# WZ8048C050-V1_1-20230407.net
KiCad netlist of a schematic drawn in EAGLE
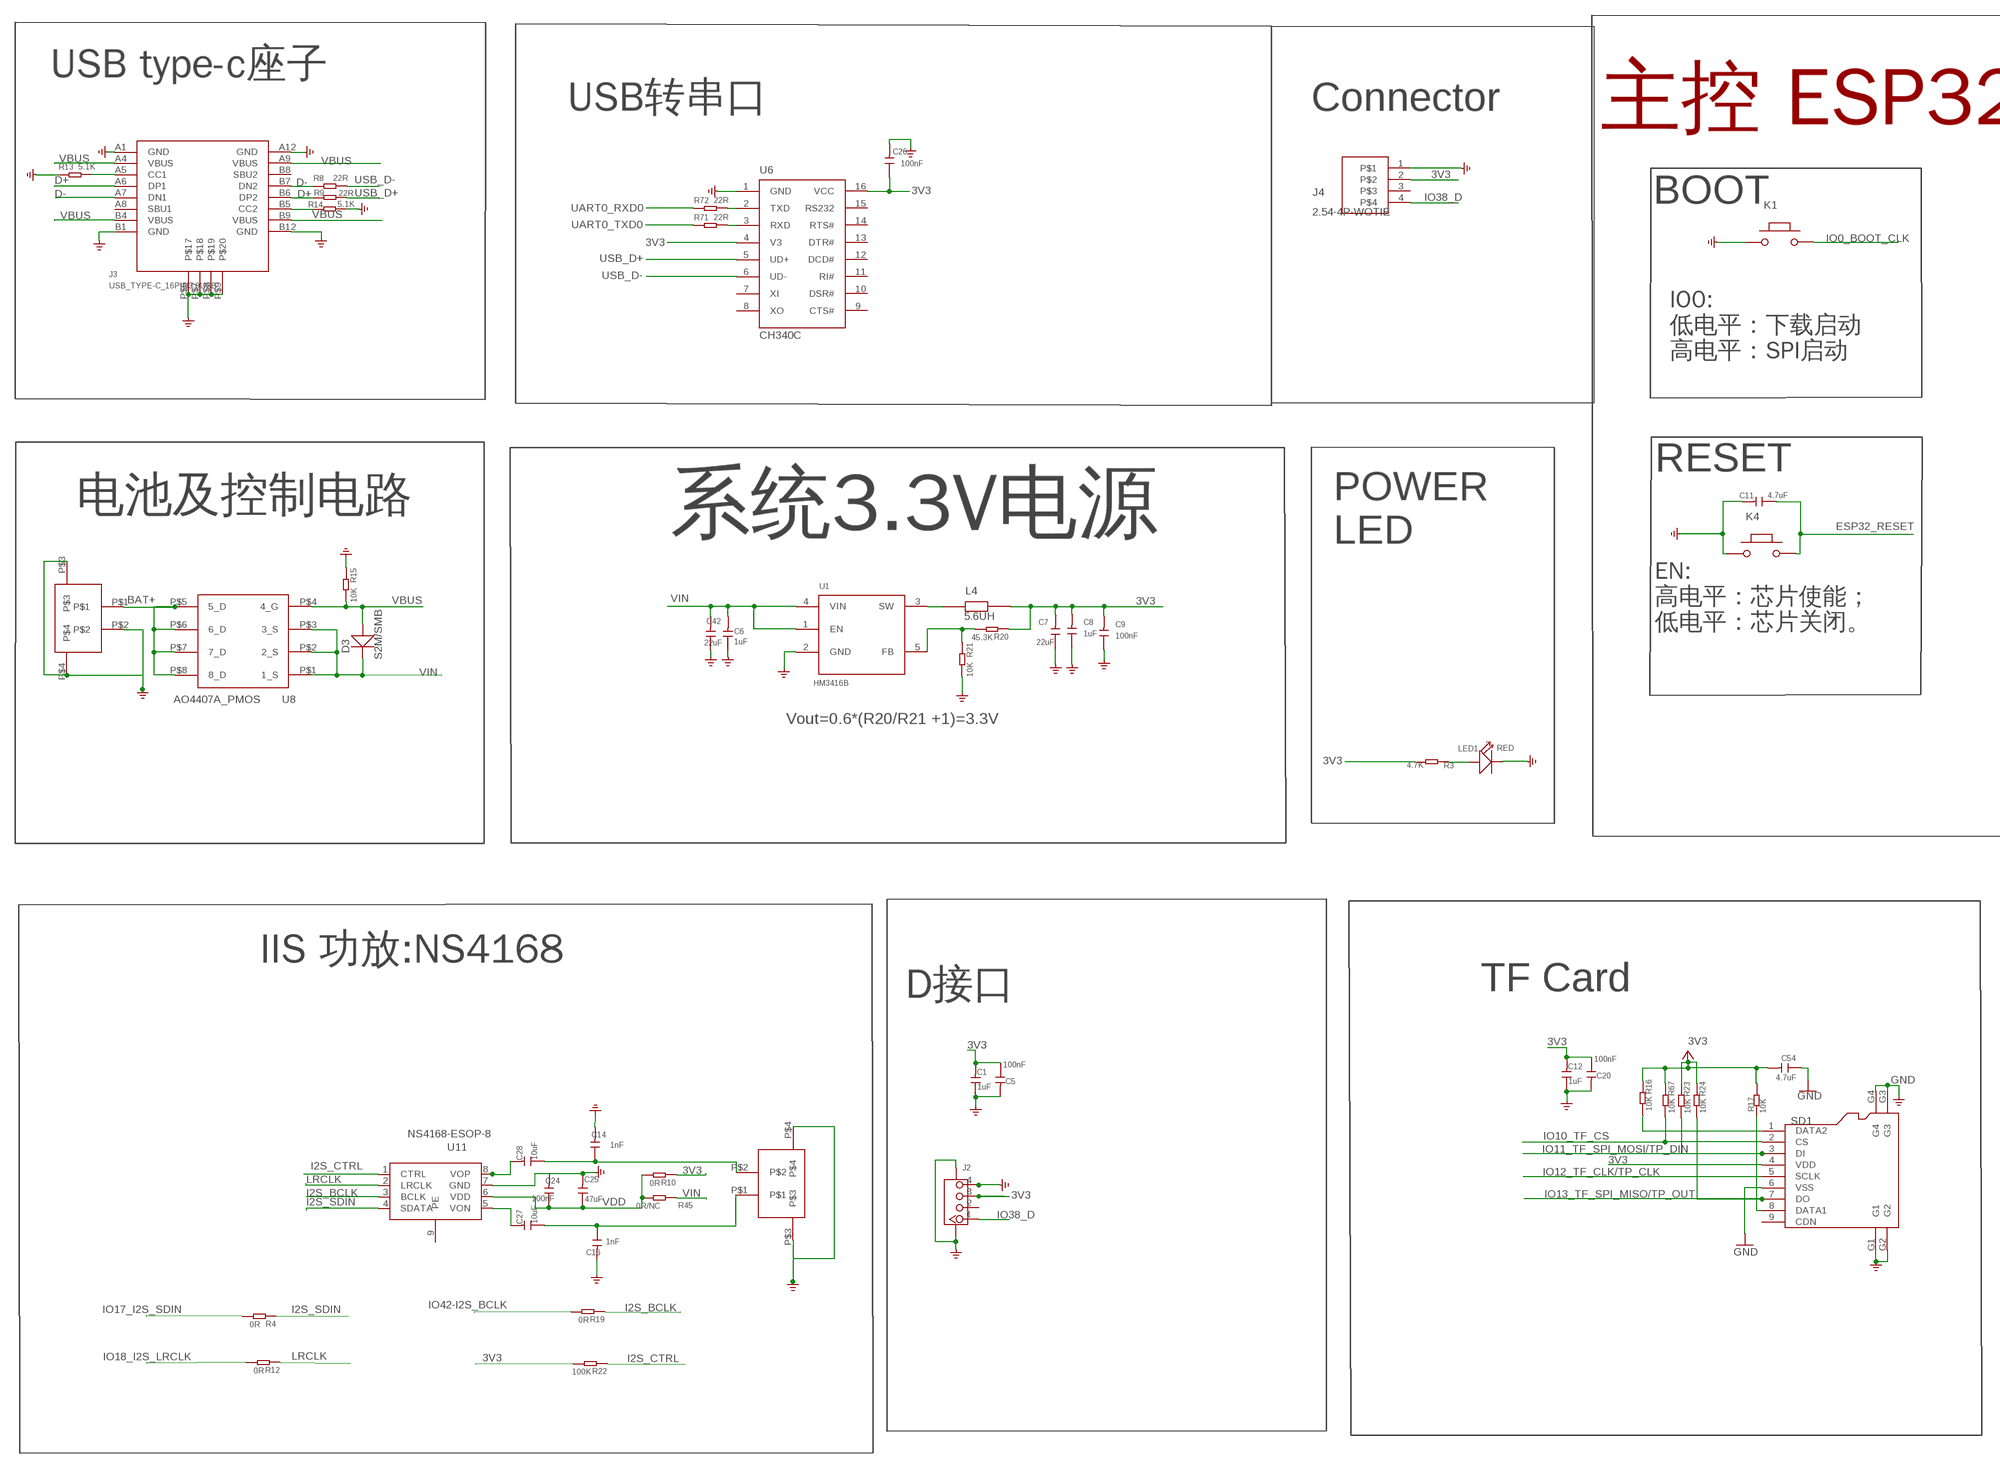
[diagram p0: schematic, sheet 1, part 1 of 2]
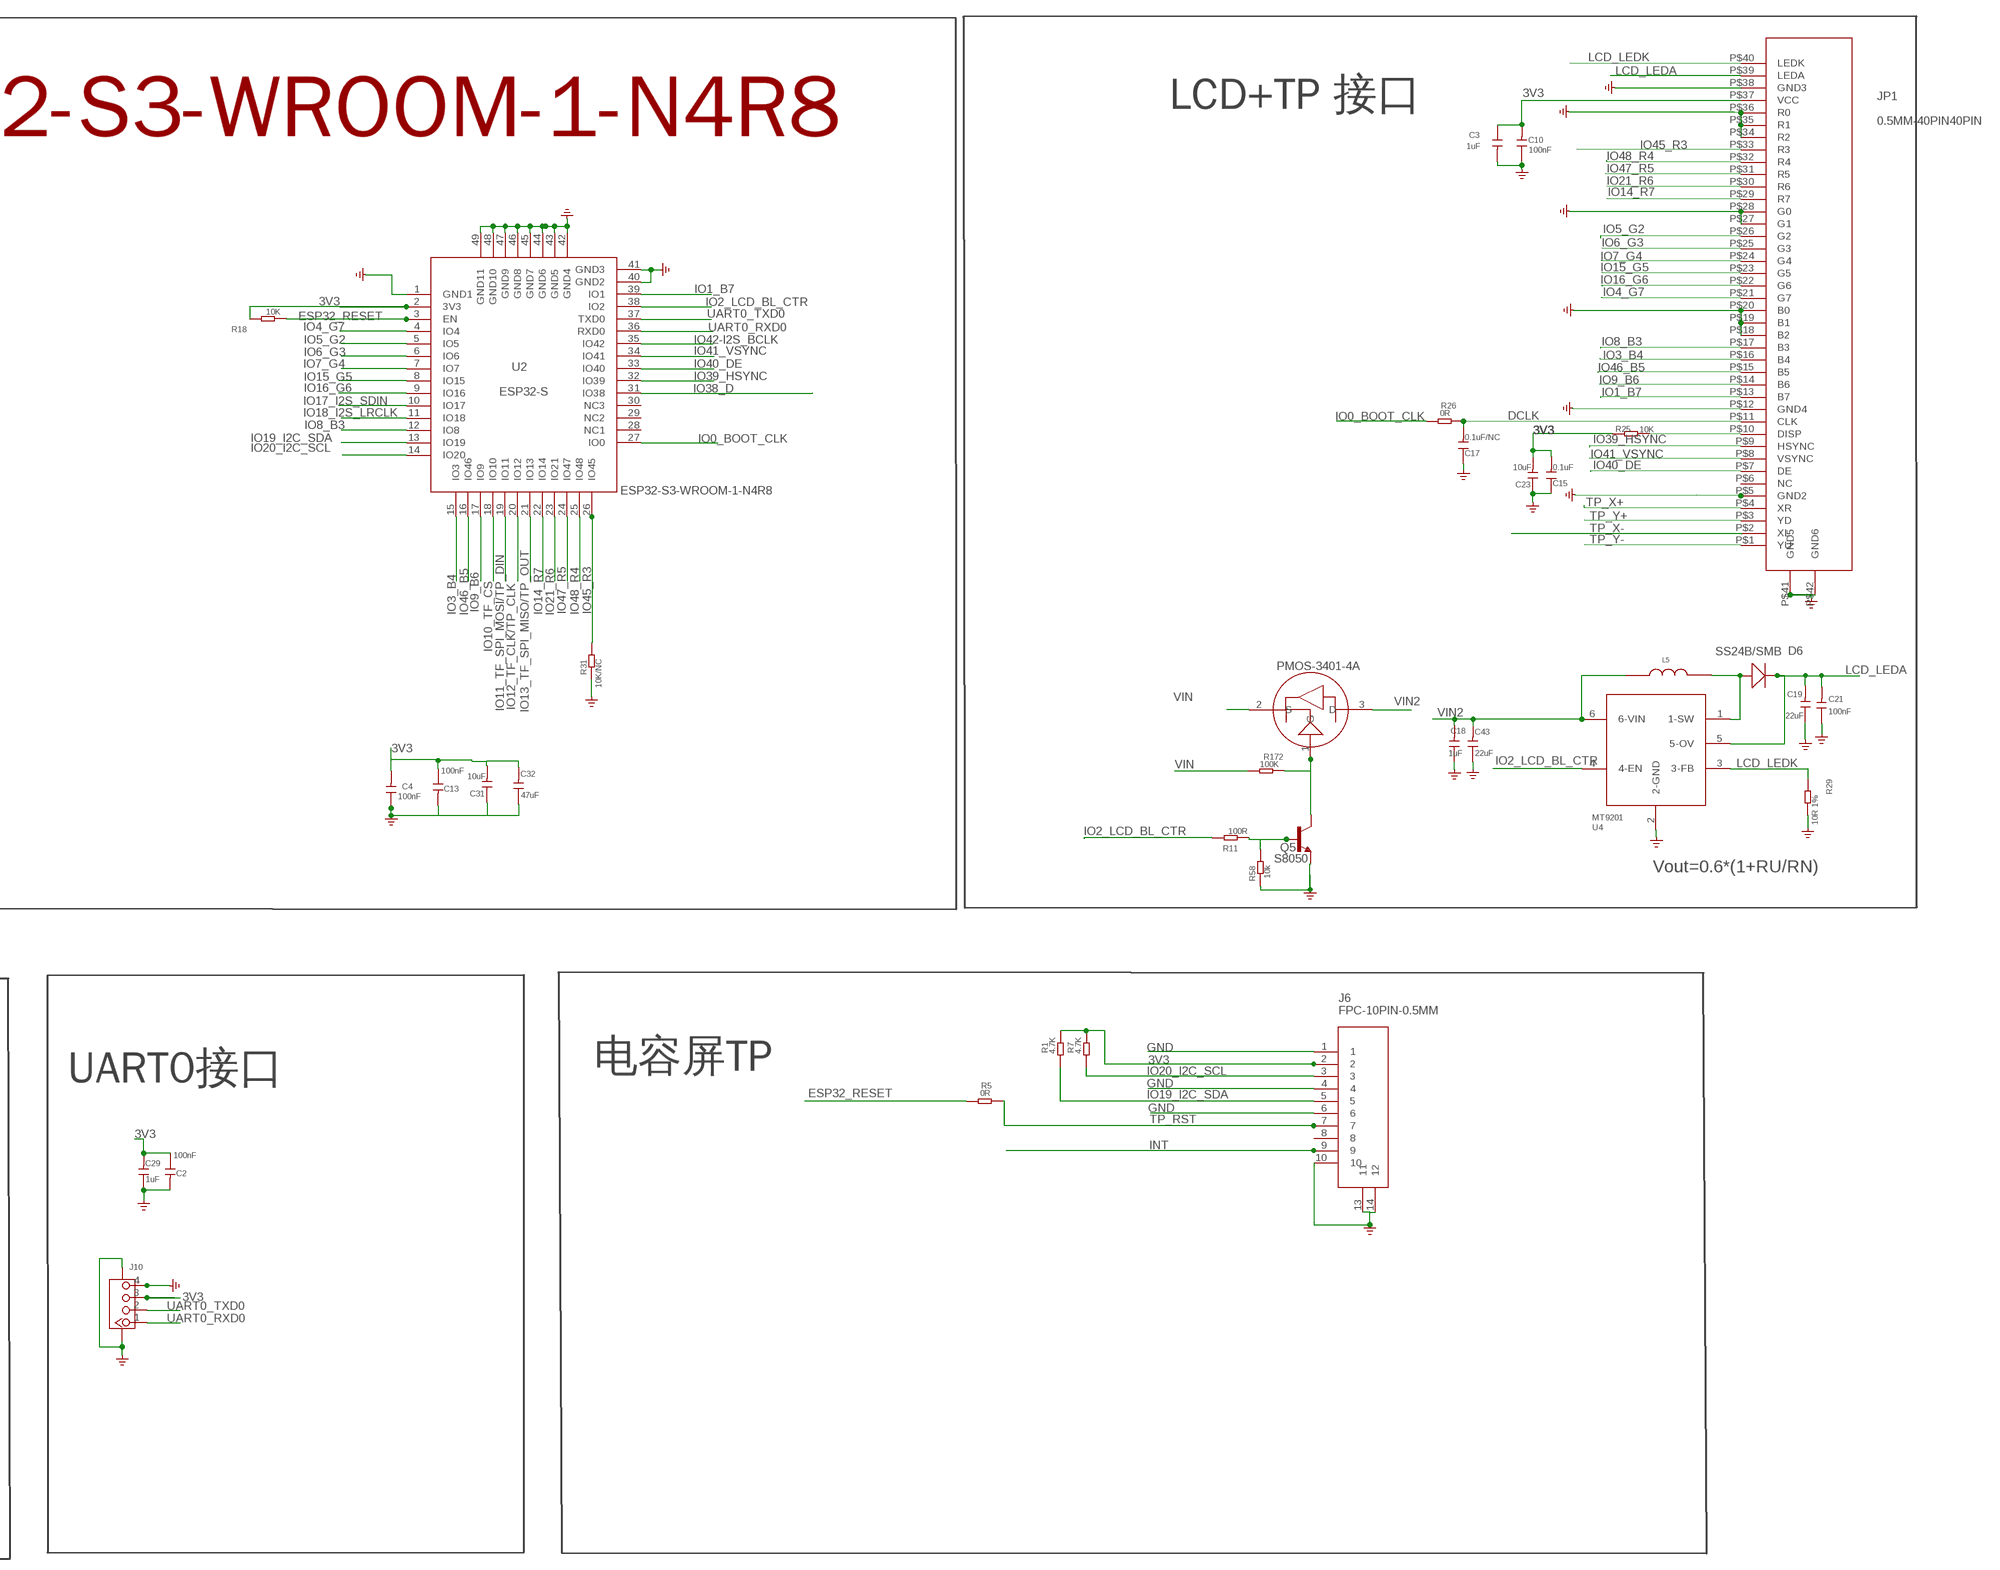
[diagram p1: schematic, sheet 1, part 2 of 2]

(export (version "E")
  (design (tool "Eeschema 10.0.6"))
  (components
    (comp (ref "C1")
      (value "1uF")
      (footprint "eagle-import:DISCRETE_C0603")
      (libsource (lib "eagle-import") (part "A_xbj_DISCRETE_C-0603"))
    )
    (comp (ref "C2")
      (value "100nF")
      (footprint "eagle-import:C0603")
      (libsource (lib "eagle-import") (part "C-0603"))
    )
    (comp (ref "C3")
      (value "1uF")
      (footprint "eagle-import:C0603")
      (libsource (lib "eagle-import") (part "C-0603"))
    )
    (comp (ref "C4")
      (value "100nF")
      (footprint "eagle-import:C0603")
      (libsource (lib "eagle-import") (part "C-0603"))
    )
    (comp (ref "C5")
      (value "100nF")
      (footprint "eagle-import:C0603")
      (libsource (lib "eagle-import") (part "C-0603"))
    )
    (comp (ref "C6")
      (value "1uF")
      (footprint "eagle-import:0603")
      (libsource (lib "eagle-import") (part "C0603"))
    )
    (comp (ref "C7")
      (value "22uF")
      (footprint "eagle-import:0805")
      (libsource (lib "eagle-import") (part "C0805"))
    )
    (comp (ref "C8")
      (value "1uF")
      (footprint "eagle-import:0603")
      (libsource (lib "eagle-import") (part "C0603"))
    )
    (comp (ref "C9")
      (value "100nF")
      (footprint "eagle-import:0603")
      (libsource (lib "eagle-import") (part "C0603"))
    )
    (comp (ref "C10")
      (value "100nF")
      (footprint "eagle-import:C0603")
      (libsource (lib "eagle-import") (part "C-0603"))
    )
    (comp (ref "C11")
      (value "4.7uF")
      (footprint "eagle-import:0603")
      (libsource (lib "eagle-import") (part "C0603"))
    )
    (comp (ref "C12")
      (value "1uF")
      (footprint "eagle-import:DISCRETE_C0603")
      (libsource (lib "eagle-import") (part "A_xbj_DISCRETE_C-0603"))
    )
    (comp (ref "C13")
      (value "100nF")
      (footprint "eagle-import:C0603")
      (libsource (lib "eagle-import") (part "C-0603"))
    )
    (comp (ref "C14")
      (value "1nF")
      (footprint "eagle-import:C0603")
      (libsource (lib "eagle-import") (part "C-0603"))
    )
    (comp (ref "C15")
      (value "0.1uF")
      (footprint "eagle-import:DISCRETE_C0603")
      (libsource (lib "eagle-import") (part "DISCRETE_C-0603"))
    )
    (comp (ref "C16")
      (value "1nF")
      (footprint "eagle-import:C0603")
      (libsource (lib "eagle-import") (part "C-0603"))
    )
    (comp (ref "C17")
      (value "0.1uF/NC")
      (footprint "eagle-import:DISCRETE_C0603")
      (libsource (lib "eagle-import") (part "DISCRETE_C-0603"))
    )
    (comp (ref "C18")
      (value "1uF")
      (footprint "eagle-import:0603")
      (libsource (lib "eagle-import") (part "C0603"))
    )
    (comp (ref "C19")
      (value "22uF")
      (footprint "eagle-import:0805")
      (libsource (lib "eagle-import") (part "C0805"))
    )
    (comp (ref "C20")
      (value "100nF")
      (footprint "eagle-import:C0603")
      (libsource (lib "eagle-import") (part "C-0603"))
    )
    (comp (ref "C21")
      (value "100nF")
      (footprint "eagle-import:0603")
      (libsource (lib "eagle-import") (part "C0603"))
    )
    (comp (ref "C23")
      (value "10uF")
      (footprint "eagle-import:DISCRETE_C0603")
      (libsource (lib "eagle-import") (part "DISCRETE_C-0603"))
    )
    (comp (ref "C24")
      (value "100nF")
      (footprint "eagle-import:C0603")
      (libsource (lib "eagle-import") (part "C-0603"))
    )
    (comp (ref "C25")
      (value "47uF")
      (footprint "eagle-import:0805")
      (libsource (lib "eagle-import") (part "C0805"))
    )
    (comp (ref "C26")
      (value "100nF")
      (footprint "eagle-import:0603")
      (libsource (lib "eagle-import") (part "C0603"))
    )
    (comp (ref "C27")
      (value "10uF")
      (footprint "eagle-import:DISCRETE_C0603")
      (libsource (lib "eagle-import") (part "A_xbj_DISCRETE_C-0603"))
    )
    (comp (ref "C28")
      (value "10uF")
      (footprint "eagle-import:DISCRETE_C0603")
      (libsource (lib "eagle-import") (part "A_xbj_DISCRETE_C-0603"))
    )
    (comp (ref "C29")
      (value "1uF")
      (footprint "eagle-import:DISCRETE_C0603")
      (libsource (lib "eagle-import") (part "A_xbj_DISCRETE_C-0603"))
    )
    (comp (ref "C31")
      (value "10uF")
      (footprint "eagle-import:DISCRETE_C0603")
      (libsource (lib "eagle-import") (part "DISCRETE_C-0603"))
    )
    (comp (ref "C32")
      (value "47uF")
      (footprint "eagle-import:0805")
      (libsource (lib "eagle-import") (part "C0805"))
    )
    (comp (ref "C42")
      (value "22uF")
      (footprint "eagle-import:0805")
      (libsource (lib "eagle-import") (part "C0805"))
    )
    (comp (ref "C43")
      (value "22uF")
      (footprint "eagle-import:0805")
      (libsource (lib "eagle-import") (part "C0805"))
    )
    (comp (ref "C54")
      (value "4.7uF")
      (footprint "eagle-import:DISCRETE_C0603")
      (libsource (lib "eagle-import") (part "DISCRETE_C-0603"))
    )
    (comp (ref "D3")
      (value "S2M/SMB")
      (footprint "eagle-import:214AB")
      (libsource (lib "eagle-import") (part "214ABDO-214AB"))
    )
    (comp (ref "D6")
      (value "SS24B/SMB")
      (footprint "eagle-import:214AB")
      (libsource (lib "eagle-import") (part "214ABDO-214AB"))
    )
    (comp (ref "J1")
      (value "PH2.0WT-2PIN")
      (footprint "eagle-import:PH2.0WT-2PIN")
      (libsource (lib "eagle-import") (part "PH2.0WT-2PIN"))
    )
    (comp (ref "J2")
      (value "CONNECTOR_TWIG-4P-2.0-SMD-FEMALE-REINFORCE90D")
      (footprint "eagle-import:CONNECTOR_4P-SMD-2.0-90D")
      (libsource (lib "eagle-import") (part "CONNECTOR_TWIG-4P-2.0-SMD-FEMALE-REINFORCE90D"))
    )
    (comp (ref "J3")
      (value "USB_TYPE-C_16PIN3.0USB")
      (footprint "eagle-import:KEVIN_3.0TYPEC-SMD")
      (libsource (lib "eagle-import") (part "USB_TYPE-C_16PIN3.0USB"))
    )
    (comp (ref "J4")
      (value "2.54-4P-WOTIE")
      (footprint "eagle-import:2.54-4P-WOTIE")
      (libsource (lib "eagle-import") (part "2.54-4P-WOTIE"))
    )
    (comp (ref "J5")
      (value "PH2.0WT-2PIN")
      (footprint "eagle-import:PH2.0WT-2PIN")
      (libsource (lib "eagle-import") (part "PH2.0WT-2PIN"))
    )
    (comp (ref "J6")
      (value "FPC-10PIN-0.5MM")
      (footprint "eagle-import:FPC-10PIN-0.5MM")
      (libsource (lib "eagle-import") (part "FPC-10PIN-0.5MM"))
    )
    (comp (ref "J10")
      (value "CONNECTOR_TWIG-4P-2.0-SMD-FEMALE-REINFORCE90D")
      (footprint "eagle-import:CONNECTOR_4P-SMD-2.0-90D")
      (libsource (lib "eagle-import") (part "CONNECTOR_TWIG-4P-2.0-SMD-FEMALE-REINFORCE90D"))
    )
    (comp (ref "JP1")
      (value "0.5MM-40PIN40PIN")
      (footprint "eagle-import:0.5MM_40P")
      (libsource (lib "eagle-import") (part "0.5MM-40PIN40PIN"))
    )
    (comp (ref "K1")
      (value "BUTTON")
      (footprint "eagle-import:157SW")
      (libsource (lib "eagle-import") (part "PB157"))
    )
    (comp (ref "K4")
      (value "BUTTON")
      (footprint "eagle-import:157SW")
      (libsource (lib "eagle-import") (part "PB157"))
    )
    (comp (ref "L4")
      (value "5.6UH")
      (footprint "eagle-import:CD54")
      (libsource (lib "eagle-import") (part "CROWPI2-MB-V1.4-20211012_CMP201209UD1R0MT"))
    )
    (comp (ref "L5")
      (value "CD32_6.8uH")
      (footprint "eagle-import:CD32")
      (libsource (lib "eagle-import") (part "CD32_950MA"))
    )
    (comp (ref "LED1")
      (value "RED")
      (footprint "eagle-import:DISCRETE_LED-0603")
      (libsource (lib "eagle-import") (part "DISCRETE_LED0603"))
    )
    (comp (ref "Q5")
      (value "S8050")
      (footprint "eagle-import:SPARKFUN_SOT23")
      (libsource (lib "eagle-import") (part "SPARKFUN_TRANSISTOR_NPNSOT23"))
    )
    (comp (ref "Q30")
      (value "PMOS-3401-4A")
      (footprint "eagle-import:SOT-23")
      (libsource (lib "eagle-import") (part "P-MOS-SOT23"))
    )
    (comp (ref "R1")
      (value "4.7K")
      (footprint "eagle-import:R0603")
      (libsource (lib "eagle-import") (part "R-0603"))
    )
    (comp (ref "R3")
      (value "4.7K")
      (footprint "eagle-import:DISCRETE_R0603")
      (libsource (lib "eagle-import") (part "DISCRETE_R-0603"))
    )
    (comp (ref "R4")
      (value "0R")
      (footprint "eagle-import:DISCRETE_R0603")
      (libsource (lib "eagle-import") (part "DISCRETE_R-0603"))
    )
    (comp (ref "R5")
      (value "0R")
      (footprint "eagle-import:R0603")
      (libsource (lib "eagle-import") (part "R-0603"))
    )
    (comp (ref "R7")
      (value "4.7K")
      (footprint "eagle-import:R0603")
      (libsource (lib "eagle-import") (part "R-0603"))
    )
    (comp (ref "R8")
      (value "22R")
      (footprint "eagle-import:DISCRETE_R0603")
      (libsource (lib "eagle-import") (part "DISCRETE_R-0603"))
    )
    (comp (ref "R9")
      (value "22R")
      (footprint "eagle-import:DISCRETE_R0603")
      (libsource (lib "eagle-import") (part "DISCRETE_R-0603"))
    )
    (comp (ref "R10")
      (value "0R")
      (footprint "eagle-import:DISCRETE_R0603")
      (libsource (lib "eagle-import") (part "DISCRETE_R-0603"))
    )
    (comp (ref "R11")
      (value "100R")
      (footprint "eagle-import:R0603")
      (libsource (lib "eagle-import") (part "R0603"))
    )
    (comp (ref "R12")
      (value "0R")
      (footprint "eagle-import:DISCRETE_R0603")
      (libsource (lib "eagle-import") (part "DISCRETE_R-0603"))
    )
    (comp (ref "R13")
      (value "5.1K")
      (footprint "eagle-import:DISCRETE_R0603")
      (libsource (lib "eagle-import") (part "DISCRETE_R-0603"))
    )
    (comp (ref "R14")
      (value "5.1K")
      (footprint "eagle-import:DISCRETE_R0603")
      (libsource (lib "eagle-import") (part "DISCRETE_R-0603"))
    )
    (comp (ref "R15")
      (value "10K")
      (footprint "eagle-import:DISCRETE_R0603")
      (libsource (lib "eagle-import") (part "DISCRETE_R-0603"))
    )
    (comp (ref "R16")
      (value "10K")
      (footprint "eagle-import:DISCRETE_R0603")
      (libsource (lib "eagle-import") (part "DISCRETE_R-0603"))
    )
    (comp (ref "R17")
      (value "10K")
      (footprint "eagle-import:DISCRETE_R0603")
      (libsource (lib "eagle-import") (part "DISCRETE_R-0603"))
    )
    (comp (ref "R18")
      (value "10K")
      (footprint "eagle-import:DISCRETE_R0603")
      (libsource (lib "eagle-import") (part "DISCRETE_R-0603"))
    )
    (comp (ref "R19")
      (value "0R")
      (footprint "eagle-import:DISCRETE_R0603")
      (libsource (lib "eagle-import") (part "DISCRETE_R-0603"))
    )
    (comp (ref "R20")
      (value "45.3K")
      (footprint "eagle-import:DISCRETE_R0603")
      (libsource (lib "eagle-import") (part "DISCRETE_R-0603"))
    )
    (comp (ref "R21")
      (value "10K")
      (footprint "eagle-import:DISCRETE_R0603")
      (libsource (lib "eagle-import") (part "DISCRETE_R-0603"))
    )
    (comp (ref "R22")
      (value "100K")
      (footprint "eagle-import:DISCRETE_R0603")
      (libsource (lib "eagle-import") (part "DISCRETE_R-0603"))
    )
    (comp (ref "R23")
      (value "10K")
      (footprint "eagle-import:DISCRETE_R0603")
      (libsource (lib "eagle-import") (part "DISCRETE_R-0603"))
    )
    (comp (ref "R24")
      (value "10K")
      (footprint "eagle-import:DISCRETE_R0603")
      (libsource (lib "eagle-import") (part "DISCRETE_R-0603"))
    )
    (comp (ref "R25")
      (value "10K")
      (footprint "eagle-import:DISCRETE_R0603")
      (libsource (lib "eagle-import") (part "DISCRETE_R-0603"))
    )
    (comp (ref "R26")
      (value "0R")
      (footprint "eagle-import:R0603")
      (libsource (lib "eagle-import") (part "R-0603"))
    )
    (comp (ref "R29")
      (value "10R 1%")
      (footprint "eagle-import:DISCRETE_R0603")
      (libsource (lib "eagle-import") (part "DISCRETE_R-0603"))
    )
    (comp (ref "R31")
      (value "10K/NC")
      (footprint "eagle-import:R0603")
      (libsource (lib "eagle-import") (part "R0603"))
    )
    (comp (ref "R45")
      (value "0R/NC")
      (footprint "eagle-import:DISCRETE_R0603")
      (libsource (lib "eagle-import") (part "DISCRETE_R-0603"))
    )
    (comp (ref "R58")
      (value "10k")
      (footprint "eagle-import:R0603")
      (libsource (lib "eagle-import") (part "R0603"))
    )
    (comp (ref "R67")
      (value "10K")
      (footprint "eagle-import:DISCRETE_R0603")
      (libsource (lib "eagle-import") (part "DISCRETE_R-0603"))
    )
    (comp (ref "R71")
      (value "22R")
      (footprint "eagle-import:DISCRETE_R0603")
      (libsource (lib "eagle-import") (part "DISCRETE_R-0603"))
    )
    (comp (ref "R72")
      (value "22R")
      (footprint "eagle-import:DISCRETE_R0603")
      (libsource (lib "eagle-import") (part "DISCRETE_R-0603"))
    )
    (comp (ref "R172")
      (value "100K")
      (footprint "eagle-import:R0603")
      (libsource (lib "eagle-import") (part "R-0603"))
    )
    (comp (ref "SD1")
      (value "HOLDER-MICROSD-9P")
      (footprint "eagle-import:9P-SMD-W_-RING")
      (libsource (lib "eagle-import") (part "HOLDER-MICROSD-9P"))
    )
    (comp (ref "U1")
      (value "HM3416B")
      (footprint "eagle-import:A_XBJ_SOT23-5")
      (libsource (lib "eagle-import") (part "A_XBJ_HM3420B"))
    )
    (comp (ref "U2")
      (value "ESP32-S")
      (footprint "eagle-import:ESP32-S3")
      (fields (field (name "U2") "ESP32-S3-WROOM-1-N4R8"))
      (libsource (lib "eagle-import") (part "ESP32-S"))
    )
    (comp (ref "U4")
      (value "MT9201")
      (footprint "eagle-import:SOT23-6")
      (libsource (lib "eagle-import") (part "MT9201"))
    )
    (comp (ref "U6")
      (value "CH340C")
      (footprint "eagle-import:SOP-16")
      (libsource (lib "eagle-import") (part "CH340G"))
    )
    (comp (ref "U8")
      (value "AO4407A_PMOS")
      (footprint "eagle-import:SOP8")
      (libsource (lib "eagle-import") (part "T_PMOS_AO4407A_SOP8"))
    )
    (comp (ref "U11")
      (value "NS4168-ESOP-8")
      (footprint "eagle-import:NS4168-ESOP-8")
      (libsource (lib "eagle-import") (part "NS4168-ESOP-8"))
    )
  )
  (nets
    (net (code "1") (name "+3V3") (class "Default")
      (node (ref "C1") (pin "2") (pinfunction "2_2") (pintype "passive"))
      (node (ref "C10") (pin "2") (pinfunction "2_2") (pintype "passive"))
      (node (ref "C12") (pin "2") (pinfunction "2_2") (pintype "passive"))
      (node (ref "C13") (pin "1") (pinfunction "1_1") (pintype "passive"))
      (node (ref "C15") (pin "2") (pinfunction "2_2") (pintype "passive"))
      (node (ref "C2") (pin "1") (pinfunction "1_1") (pintype "passive"))
      (node (ref "C20") (pin "1") (pinfunction "1_1") (pintype "passive"))
      (node (ref "C23") (pin "2") (pinfunction "2_2") (pintype "passive"))
      (node (ref "C26") (pin "1") (pinfunction "1_1") (pintype "passive"))
      (node (ref "C29") (pin "2") (pinfunction "2_2") (pintype "passive"))
      (node (ref "C3") (pin "1") (pinfunction "1_1") (pintype "passive"))
      (node (ref "C31") (pin "2") (pinfunction "2_2") (pintype "passive"))
      (node (ref "C32") (pin "2") (pinfunction "2_2") (pintype "passive"))
      (node (ref "C4") (pin "2") (pinfunction "2_2") (pintype "passive"))
      (node (ref "C5") (pin "1") (pinfunction "1_1") (pintype "passive"))
      (node (ref "C54") (pin "2") (pinfunction "2_2") (pintype "passive"))
      (node (ref "C7") (pin "2") (pinfunction "2_2") (pintype "passive"))
      (node (ref "C8") (pin "2") (pinfunction "2_2") (pintype "passive"))
      (node (ref "C9") (pin "2") (pinfunction "2_2") (pintype "passive"))
      (node (ref "J10") (pin "3") (pinfunction "3_3") (pintype "bidirectional"))
      (node (ref "J2") (pin "3") (pinfunction "3_3") (pintype "bidirectional"))
      (node (ref "J4") (pin "2") (pinfunction "P$2_2") (pintype "bidirectional"))
      (node (ref "J6") (pin "2") (pinfunction "2_2") (pintype "bidirectional"))
      (node (ref "JP1") (pin "P$37") (pinfunction "VCC_P$37") (pintype "bidirectional"))
      (node (ref "L4") (pin "2") (pinfunction "2_2") (pintype "bidirectional"))
      (node (ref "R1") (pin "2") (pinfunction "2_2") (pintype "passive"))
      (node (ref "R10") (pin "1") (pinfunction "1_1") (pintype "passive"))
      (node (ref "R16") (pin "1") (pinfunction "1_1") (pintype "passive"))
      (node (ref "R17") (pin "1") (pinfunction "1_1") (pintype "passive"))
      (node (ref "R18") (pin "1") (pinfunction "1_1") (pintype "passive"))
      (node (ref "R20") (pin "1") (pinfunction "1_1") (pintype "passive"))
      (node (ref "R22") (pin "2") (pinfunction "2_2") (pintype "passive"))
      (node (ref "R23") (pin "1") (pinfunction "1_1") (pintype "passive"))
      (node (ref "R24") (pin "1") (pinfunction "1_1") (pintype "passive"))
      (node (ref "R25") (pin "1") (pinfunction "1_1") (pintype "passive"))
      (node (ref "R3") (pin "2") (pinfunction "2_2") (pintype "passive"))
      (node (ref "R67") (pin "1") (pinfunction "1_1") (pintype "passive"))
      (node (ref "R7") (pin "2") (pinfunction "2_2") (pintype "passive"))
      (node (ref "SD1") (pin "4") (pinfunction "VDD_4") (pintype "bidirectional"))
      (node (ref "U2") (pin "2") (pinfunction "3V3_2") (pintype "bidirectional"))
      (node (ref "U6") (pin "16") (pinfunction "VCC_16") (pintype "bidirectional"))
      (node (ref "U6") (pin "4") (pinfunction "V3_4") (pintype "bidirectional"))
    )
    (net (code "2") (name "/BAT+") (class "Default")
      (node (ref "J1") (pin "P$1") (pinfunction "P$1_P$1") (pintype "bidirectional"))
      (node (ref "U8") (pin "P$5") (pinfunction "5_D_P$5") (pintype "bidirectional"))
      (node (ref "U8") (pin "P$6") (pinfunction "6_D_P$6") (pintype "bidirectional"))
      (node (ref "U8") (pin "P$7") (pinfunction "7_D_P$7") (pintype "bidirectional"))
      (node (ref "U8") (pin "P$8") (pinfunction "8_D_P$8") (pintype "bidirectional"))
    )
    (net (code "3") (name "/D+") (class "Default")
      (node (ref "J3") (pin "A6") (pinfunction "DP1_A6") (pintype "bidirectional"))
      (node (ref "J3") (pin "B6") (pinfunction "DP2_B6") (pintype "bidirectional"))
      (node (ref "R9") (pin "1") (pinfunction "1_1") (pintype "passive"))
    )
    (net (code "4") (name "/D-") (class "Default")
      (node (ref "J3") (pin "A7") (pinfunction "DN1_A7") (pintype "bidirectional"))
      (node (ref "J3") (pin "B7") (pinfunction "DN2_B7") (pintype "bidirectional"))
      (node (ref "R8") (pin "1") (pinfunction "1_1") (pintype "passive"))
    )
    (net (code "5") (name "/DCLK") (class "Default")
      (node (ref "C17") (pin "2") (pinfunction "2_2") (pintype "passive"))
      (node (ref "JP1") (pin "P$11") (pinfunction "CLK_P$11") (pintype "bidirectional"))
      (node (ref "R26") (pin "2") (pinfunction "2_2") (pintype "passive"))
    )
    (net (code "6") (name "/ESP32_RESET") (class "Default")
      (node (ref "C11") (pin "1") (pinfunction "1_1") (pintype "passive"))
      (node (ref "K4") (pin "2") (pinfunction "2_2") (pintype "passive"))
      (node (ref "R18") (pin "2") (pinfunction "2_2") (pintype "passive"))
      (node (ref "R5") (pin "1") (pinfunction "1_1") (pintype "passive"))
      (node (ref "U2") (pin "3") (pinfunction "EN_3") (pintype "bidirectional"))
    )
    (net (code "7") (name "/I2S_BCLK") (class "Default")
      (node (ref "R19") (pin "1") (pinfunction "1_1") (pintype "passive"))
      (node (ref "U11") (pin "3") (pinfunction "BCLK_3") (pintype "bidirectional"))
    )
    (net (code "8") (name "/I2S_CTRL") (class "Default")
      (node (ref "R22") (pin "1") (pinfunction "1_1") (pintype "passive"))
      (node (ref "U11") (pin "1") (pinfunction "CTRL_1") (pintype "bidirectional"))
    )
    (net (code "9") (name "/I2S_SDIN") (class "Default")
      (node (ref "R4") (pin "1") (pinfunction "1_1") (pintype "passive"))
      (node (ref "U11") (pin "4") (pinfunction "SDATA_4") (pintype "bidirectional"))
    )
    (net (code "10") (name "/INT") (class "Default")
      (node (ref "J6") (pin "9") (pinfunction "9_9") (pintype "bidirectional"))
    )
    (net (code "11") (name "/IO0_BOOT_CLK") (class "Default")
      (node (ref "K1") (pin "2") (pinfunction "2_2") (pintype "passive"))
      (node (ref "R26") (pin "1") (pinfunction "1_1") (pintype "passive"))
      (node (ref "U2") (pin "27") (pinfunction "IO0_27") (pintype "bidirectional"))
    )
    (net (code "12") (name "/IO1_B7") (class "Default")
      (node (ref "JP1") (pin "P$13") (pinfunction "B7_P$13") (pintype "bidirectional"))
      (node (ref "U2") (pin "39") (pinfunction "IO1_39") (pintype "bidirectional"))
    )
    (net (code "13") (name "/IO2_LCD_BL_CTR") (class "Default")
      (node (ref "R11") (pin "2") (pinfunction "2_2") (pintype "passive"))
      (node (ref "U2") (pin "38") (pinfunction "IO2_38") (pintype "bidirectional"))
      (node (ref "U4") (pin "4") (pinfunction "4-EN_4") (pintype "bidirectional"))
    )
    (net (code "14") (name "/IO3_B4") (class "Default")
      (node (ref "JP1") (pin "P$16") (pinfunction "B4_P$16") (pintype "bidirectional"))
      (node (ref "U2") (pin "15") (pinfunction "IO3_15") (pintype "bidirectional"))
    )
    (net (code "15") (name "/IO4_G7") (class "Default")
      (node (ref "JP1") (pin "P$21") (pinfunction "G7_P$21") (pintype "bidirectional"))
      (node (ref "U2") (pin "4") (pinfunction "IO4_4") (pintype "bidirectional"))
    )
    (net (code "16") (name "/IO5_G2") (class "Default")
      (node (ref "JP1") (pin "P$26") (pinfunction "G2_P$26") (pintype "bidirectional"))
      (node (ref "U2") (pin "5") (pinfunction "IO5_5") (pintype "bidirectional"))
    )
    (net (code "17") (name "/IO6_G3") (class "Default")
      (node (ref "JP1") (pin "P$25") (pinfunction "G3_P$25") (pintype "bidirectional"))
      (node (ref "U2") (pin "6") (pinfunction "IO6_6") (pintype "bidirectional"))
    )
    (net (code "18") (name "/IO7_G4") (class "Default")
      (node (ref "JP1") (pin "P$24") (pinfunction "G4_P$24") (pintype "bidirectional"))
      (node (ref "U2") (pin "7") (pinfunction "IO7_7") (pintype "bidirectional"))
    )
    (net (code "19") (name "/IO8_B3") (class "Default")
      (node (ref "JP1") (pin "P$17") (pinfunction "B3_P$17") (pintype "bidirectional"))
      (node (ref "U2") (pin "12") (pinfunction "IO8_12") (pintype "bidirectional"))
    )
    (net (code "20") (name "/IO9_B6") (class "Default")
      (node (ref "JP1") (pin "P$14") (pinfunction "B6_P$14") (pintype "bidirectional"))
      (node (ref "U2") (pin "17") (pinfunction "IO9_17") (pintype "bidirectional"))
    )
    (net (code "21") (name "/IO10_TF_CS") (class "Default")
      (node (ref "R67") (pin "2") (pinfunction "2_2") (pintype "passive"))
      (node (ref "SD1") (pin "2") (pinfunction "CS_2") (pintype "bidirectional"))
      (node (ref "U2") (pin "18") (pinfunction "IO10_18") (pintype "bidirectional"))
    )
    (net (code "22") (name "/IO11_TF_SPI_MOSI{slash}TP_DIN") (class "Default")
      (node (ref "R23") (pin "2") (pinfunction "2_2") (pintype "passive"))
      (node (ref "SD1") (pin "3") (pinfunction "DI_3") (pintype "bidirectional"))
      (node (ref "U2") (pin "19") (pinfunction "IO11_19") (pintype "bidirectional"))
    )
    (net (code "23") (name "/IO12_TF_CLK{slash}TP_CLK") (class "Default")
      (node (ref "SD1") (pin "5") (pinfunction "SCLK_5") (pintype "bidirectional"))
      (node (ref "U2") (pin "20") (pinfunction "IO12_20") (pintype "bidirectional"))
    )
    (net (code "24") (name "/IO13_TF_SPI_MISO{slash}TP_OUT") (class "Default")
      (node (ref "R24") (pin "2") (pinfunction "2_2") (pintype "passive"))
      (node (ref "SD1") (pin "7") (pinfunction "DO_7") (pintype "bidirectional"))
      (node (ref "U2") (pin "21") (pinfunction "IO13_21") (pintype "bidirectional"))
    )
    (net (code "25") (name "/IO14_R7") (class "Default")
      (node (ref "JP1") (pin "P$29") (pinfunction "R7_P$29") (pintype "bidirectional"))
      (node (ref "U2") (pin "22") (pinfunction "IO14_22") (pintype "bidirectional"))
    )
    (net (code "26") (name "/IO15_G5") (class "Default")
      (node (ref "JP1") (pin "P$23") (pinfunction "G5_P$23") (pintype "bidirectional"))
      (node (ref "U2") (pin "8") (pinfunction "IO15_8") (pintype "bidirectional"))
    )
    (net (code "27") (name "/IO16_G6") (class "Default")
      (node (ref "JP1") (pin "P$22") (pinfunction "G6_P$22") (pintype "bidirectional"))
      (node (ref "U2") (pin "9") (pinfunction "IO16_9") (pintype "bidirectional"))
    )
    (net (code "28") (name "/IO17_I2S_SDIN") (class "Default")
      (node (ref "R4") (pin "2") (pinfunction "2_2") (pintype "passive"))
      (node (ref "U2") (pin "10") (pinfunction "IO17_10") (pintype "bidirectional"))
    )
    (net (code "29") (name "/IO18_I2S_LRCLK") (class "Default")
      (node (ref "R12") (pin "2") (pinfunction "2_2") (pintype "passive"))
      (node (ref "U2") (pin "11") (pinfunction "IO18_11") (pintype "bidirectional"))
    )
    (net (code "30") (name "/IO19_I2C_SDA") (class "Default")
      (node (ref "J6") (pin "5") (pinfunction "5_5") (pintype "bidirectional"))
      (node (ref "R1") (pin "1") (pinfunction "1_1") (pintype "passive"))
      (node (ref "U2") (pin "13") (pinfunction "IO19_13") (pintype "bidirectional"))
    )
    (net (code "31") (name "/IO20_I2C_SCL") (class "Default")
      (node (ref "J6") (pin "3") (pinfunction "3_3") (pintype "bidirectional"))
      (node (ref "R7") (pin "1") (pinfunction "1_1") (pintype "passive"))
      (node (ref "U2") (pin "14") (pinfunction "IO20_14") (pintype "bidirectional"))
    )
    (net (code "32") (name "/IO21_R6") (class "Default")
      (node (ref "JP1") (pin "P$30") (pinfunction "R6_P$30") (pintype "bidirectional"))
      (node (ref "U2") (pin "23") (pinfunction "IO21_23") (pintype "bidirectional"))
    )
    (net (code "33") (name "/IO38_D") (class "Default")
      (node (ref "J2") (pin "1") (pinfunction "1_1") (pintype "bidirectional"))
      (node (ref "J4") (pin "4") (pinfunction "P$4_4") (pintype "bidirectional"))
      (node (ref "U2") (pin "31") (pinfunction "IO38_31") (pintype "bidirectional"))
    )
    (net (code "34") (name "/IO39_HSYNC") (class "Default")
      (node (ref "JP1") (pin "P$9") (pinfunction "HSYNC_P$9") (pintype "bidirectional"))
      (node (ref "U2") (pin "32") (pinfunction "IO39_32") (pintype "bidirectional"))
    )
    (net (code "35") (name "/IO40_DE") (class "Default")
      (node (ref "JP1") (pin "P$7") (pinfunction "DE_P$7") (pintype "bidirectional"))
      (node (ref "U2") (pin "33") (pinfunction "IO40_33") (pintype "bidirectional"))
    )
    (net (code "36") (name "/IO41_VSYNC") (class "Default")
      (node (ref "JP1") (pin "P$8") (pinfunction "VSYNC_P$8") (pintype "bidirectional"))
      (node (ref "U2") (pin "34") (pinfunction "IO41_34") (pintype "bidirectional"))
    )
    (net (code "37") (name "/IO42-I2S_BCLK") (class "Default")
      (node (ref "R19") (pin "2") (pinfunction "2_2") (pintype "passive"))
      (node (ref "U2") (pin "35") (pinfunction "IO42_35") (pintype "bidirectional"))
    )
    (net (code "38") (name "/IO45_R3") (class "Default")
      (node (ref "JP1") (pin "P$33") (pinfunction "R3_P$33") (pintype "bidirectional"))
      (node (ref "R31") (pin "2") (pinfunction "2_2") (pintype "passive"))
      (node (ref "U2") (pin "26") (pinfunction "IO45_26") (pintype "bidirectional"))
    )
    (net (code "39") (name "/IO46_B5") (class "Default")
      (node (ref "JP1") (pin "P$15") (pinfunction "B5_P$15") (pintype "bidirectional"))
      (node (ref "U2") (pin "16") (pinfunction "IO46_16") (pintype "bidirectional"))
    )
    (net (code "40") (name "/IO47_R5") (class "Default")
      (node (ref "JP1") (pin "P$31") (pinfunction "R5_P$31") (pintype "bidirectional"))
      (node (ref "U2") (pin "24") (pinfunction "IO47_24") (pintype "bidirectional"))
    )
    (net (code "41") (name "/IO48_R4") (class "Default")
      (node (ref "JP1") (pin "P$32") (pinfunction "R4_P$32") (pintype "bidirectional"))
      (node (ref "U2") (pin "25") (pinfunction "IO48_25") (pintype "bidirectional"))
    )
    (net (code "42") (name "/LCD_LEDA") (class "Default")
      (node (ref "C19") (pin "2") (pinfunction "2_2") (pintype "passive"))
      (node (ref "C21") (pin "2") (pinfunction "2_2") (pintype "passive"))
      (node (ref "D6") (pin "2") (pinfunction "-_2") (pintype "passive"))
      (node (ref "JP1") (pin "P$39") (pinfunction "LEDA_P$39") (pintype "bidirectional"))
      (node (ref "U4") (pin "5") (pinfunction "5-OV_5") (pintype "bidirectional"))
    )
    (net (code "43") (name "/LCD_LEDK") (class "Default")
      (node (ref "JP1") (pin "P$40") (pinfunction "LEDK_P$40") (pintype "bidirectional"))
      (node (ref "R29") (pin "1") (pinfunction "1_1") (pintype "passive"))
      (node (ref "U4") (pin "3") (pinfunction "3-FB_3") (pintype "bidirectional"))
    )
    (net (code "44") (name "/LRCLK") (class "Default")
      (node (ref "R12") (pin "1") (pinfunction "1_1") (pintype "passive"))
      (node (ref "U11") (pin "2") (pinfunction "LRCLK_2") (pintype "bidirectional"))
    )
    (net (code "45") (name "/TP_RST") (class "Default")
      (node (ref "J6") (pin "7") (pinfunction "7_7") (pintype "bidirectional"))
      (node (ref "R5") (pin "2") (pinfunction "2_2") (pintype "passive"))
    )
    (net (code "46") (name "/TP_X+") (class "Default")
      (node (ref "JP1") (pin "P$4") (pinfunction "XR_P$4") (pintype "bidirectional"))
    )
    (net (code "47") (name "/TP_X-") (class "Default")
      (node (ref "JP1") (pin "P$2") (pinfunction "XL_P$2") (pintype "bidirectional"))
    )
    (net (code "48") (name "/TP_Y+") (class "Default")
      (node (ref "JP1") (pin "P$3") (pinfunction "YD_P$3") (pintype "bidirectional"))
    )
    (net (code "49") (name "/TP_Y-") (class "Default")
      (node (ref "JP1") (pin "P$1") (pinfunction "YU_P$1") (pintype "bidirectional"))
    )
    (net (code "50") (name "/UART0_RXD0") (class "Default")
      (node (ref "J10") (pin "1") (pinfunction "1_1") (pintype "bidirectional"))
      (node (ref "R72") (pin "1") (pinfunction "1_1") (pintype "passive"))
      (node (ref "U2") (pin "36") (pinfunction "RXD0_36") (pintype "bidirectional"))
    )
    (net (code "51") (name "/UART0_TXD0") (class "Default")
      (node (ref "J10") (pin "2") (pinfunction "2_2") (pintype "bidirectional"))
      (node (ref "R71") (pin "1") (pinfunction "1_1") (pintype "passive"))
      (node (ref "U2") (pin "37") (pinfunction "TXD0_37") (pintype "bidirectional"))
    )
    (net (code "52") (name "/USB_D+") (class "Default")
      (node (ref "R9") (pin "2") (pinfunction "2_2") (pintype "passive"))
      (node (ref "U6") (pin "5") (pinfunction "UD+_5") (pintype "bidirectional"))
    )
    (net (code "53") (name "/USB_D-") (class "Default")
      (node (ref "R8") (pin "2") (pinfunction "2_2") (pintype "passive"))
      (node (ref "U6") (pin "6") (pinfunction "UD-_6") (pintype "bidirectional"))
    )
    (net (code "54") (name "/VBUS") (class "Default")
      (node (ref "D3") (pin "1") (pinfunction "+_1") (pintype "passive"))
      (node (ref "J3") (pin "A4") (pinfunction "VBUS_A4") (pintype "bidirectional"))
      (node (ref "J3") (pin "A9") (pinfunction "VBUS_A9") (pintype "bidirectional"))
      (node (ref "J3") (pin "B4") (pinfunction "VBUS_B4") (pintype "bidirectional"))
      (node (ref "J3") (pin "B9") (pinfunction "VBUS_B9") (pintype "bidirectional"))
      (node (ref "R15") (pin "2") (pinfunction "2_2") (pintype "passive"))
      (node (ref "U8") (pin "P$4") (pinfunction "4_G_P$4") (pintype "bidirectional"))
    )
    (net (code "55") (name "/VDD") (class "Default")
      (node (ref "C24") (pin "1") (pinfunction "1_1") (pintype "passive"))
      (node (ref "C25") (pin "1") (pinfunction "1_1") (pintype "passive"))
      (node (ref "R10") (pin "2") (pinfunction "2_2") (pintype "passive"))
      (node (ref "R45") (pin "2") (pinfunction "2_2") (pintype "passive"))
      (node (ref "U11") (pin "6") (pinfunction "VDD_6") (pintype "bidirectional"))
    )
    (net (code "56") (name "/VIN") (class "Default")
      (node (ref "C42") (pin "2") (pinfunction "2_2") (pintype "passive"))
      (node (ref "C6") (pin "2") (pinfunction "2_2") (pintype "passive"))
      (node (ref "D3") (pin "2") (pinfunction "-_2") (pintype "passive"))
      (node (ref "Q30") (pin "2") (pinfunction "S_2") (pintype "bidirectional"))
      (node (ref "R172") (pin "1") (pinfunction "1_1") (pintype "passive"))
      (node (ref "R45") (pin "1") (pinfunction "1_1") (pintype "passive"))
      (node (ref "U1") (pin "1") (pinfunction "EN_1") (pintype "bidirectional"))
      (node (ref "U1") (pin "4") (pinfunction "VIN_4") (pintype "bidirectional"))
      (node (ref "U8") (pin "P$1") (pinfunction "1_S_P$1") (pintype "bidirectional"))
      (node (ref "U8") (pin "P$2") (pinfunction "2_S_P$2") (pintype "bidirectional"))
      (node (ref "U8") (pin "P$3") (pinfunction "3_S_P$3") (pintype "bidirectional"))
    )
    (net (code "57") (name "/VIN2") (class "Default")
      (node (ref "C18") (pin "2") (pinfunction "2_2") (pintype "passive"))
      (node (ref "C43") (pin "2") (pinfunction "2_2") (pintype "passive"))
      (node (ref "L5") (pin "1") (pinfunction "1_1") (pintype "bidirectional"))
      (node (ref "Q30") (pin "3") (pinfunction "D_3") (pintype "bidirectional"))
      (node (ref "U4") (pin "6") (pinfunction "6-VIN_6") (pintype "bidirectional"))
    )
    (net (code "58") (name "GND") (class "Default")
      (node (ref "C1") (pin "1") (pinfunction "1_1") (pintype "passive"))
      (node (ref "C10") (pin "1") (pinfunction "1_1") (pintype "passive"))
      (node (ref "C11") (pin "2") (pinfunction "2_2") (pintype "passive"))
      (node (ref "C12") (pin "1") (pinfunction "1_1") (pintype "passive"))
      (node (ref "C13") (pin "2") (pinfunction "2_2") (pintype "passive"))
      (node (ref "C14") (pin "2") (pinfunction "2_2") (pintype "passive"))
      (node (ref "C15") (pin "1") (pinfunction "1_1") (pintype "passive"))
      (node (ref "C16") (pin "2") (pinfunction "2_2") (pintype "passive"))
      (node (ref "C17") (pin "1") (pinfunction "1_1") (pintype "passive"))
      (node (ref "C18") (pin "1") (pinfunction "1_1") (pintype "passive"))
      (node (ref "C19") (pin "1") (pinfunction "1_1") (pintype "passive"))
      (node (ref "C2") (pin "2") (pinfunction "2_2") (pintype "passive"))
      (node (ref "C20") (pin "2") (pinfunction "2_2") (pintype "passive"))
      (node (ref "C21") (pin "1") (pinfunction "1_1") (pintype "passive"))
      (node (ref "C23") (pin "1") (pinfunction "1_1") (pintype "passive"))
      (node (ref "C24") (pin "2") (pinfunction "2_2") (pintype "passive"))
      (node (ref "C25") (pin "2") (pinfunction "2_2") (pintype "passive"))
      (node (ref "C26") (pin "2") (pinfunction "2_2") (pintype "passive"))
      (node (ref "C29") (pin "1") (pinfunction "1_1") (pintype "passive"))
      (node (ref "C3") (pin "2") (pinfunction "2_2") (pintype "passive"))
      (node (ref "C31") (pin "1") (pinfunction "1_1") (pintype "passive"))
      (node (ref "C32") (pin "1") (pinfunction "1_1") (pintype "passive"))
      (node (ref "C4") (pin "1") (pinfunction "1_1") (pintype "passive"))
      (node (ref "C42") (pin "1") (pinfunction "1_1") (pintype "passive"))
      (node (ref "C43") (pin "1") (pinfunction "1_1") (pintype "passive"))
      (node (ref "C5") (pin "2") (pinfunction "2_2") (pintype "passive"))
      (node (ref "C54") (pin "1") (pinfunction "1_1") (pintype "passive"))
      (node (ref "C6") (pin "1") (pinfunction "1_1") (pintype "passive"))
      (node (ref "C7") (pin "1") (pinfunction "1_1") (pintype "passive"))
      (node (ref "C8") (pin "1") (pinfunction "1_1") (pintype "passive"))
      (node (ref "C9") (pin "1") (pinfunction "1_1") (pintype "passive"))
      (node (ref "J1") (pin "P$2") (pinfunction "P$2_P$2") (pintype "bidirectional"))
      (node (ref "J1") (pin "P$3") (pinfunction "P$3_P$3") (pintype "bidirectional"))
      (node (ref "J1") (pin "P$4") (pinfunction "P$4_P$4") (pintype "bidirectional"))
      (node (ref "J10") (pin "4") (pinfunction "4_4") (pintype "bidirectional"))
      (node (ref "J10") (pin "SS1") (pinfunction "SS1_SS1") (pintype "bidirectional"))
      (node (ref "J10") (pin "SS2") (pinfunction "SS2_SS2") (pintype "bidirectional"))
      (node (ref "J2") (pin "4") (pinfunction "4_4") (pintype "bidirectional"))
      (node (ref "J2") (pin "SS1") (pinfunction "SS1_SS1") (pintype "bidirectional"))
      (node (ref "J2") (pin "SS2") (pinfunction "SS2_SS2") (pintype "bidirectional"))
      (node (ref "J3") (pin "A1") (pinfunction "GND_A1") (pintype "bidirectional"))
      (node (ref "J3") (pin "A12") (pinfunction "GND_A12") (pintype "bidirectional"))
      (node (ref "J3") (pin "B1") (pinfunction "GND_B1") (pintype "bidirectional"))
      (node (ref "J3") (pin "B12") (pinfunction "GND_B12") (pintype "bidirectional"))
      (node (ref "J3") (pin "P$6") (pinfunction "P$17_P$6") (pintype "bidirectional"))
      (node (ref "J3") (pin "P$7") (pinfunction "P$18_P$7") (pintype "bidirectional"))
      (node (ref "J3") (pin "P$8") (pinfunction "P$19_P$8") (pintype "bidirectional"))
      (node (ref "J3") (pin "P$9") (pinfunction "P$20_P$9") (pintype "bidirectional"))
      (node (ref "J4") (pin "1") (pinfunction "P$1_1") (pintype "bidirectional"))
      (node (ref "J5") (pin "P$3") (pinfunction "P$3_P$3") (pintype "bidirectional"))
      (node (ref "J5") (pin "P$4") (pinfunction "P$4_P$4") (pintype "bidirectional"))
      (node (ref "J6") (pin "1") (pinfunction "1_1") (pintype "bidirectional"))
      (node (ref "J6") (pin "10") (pinfunction "10_10") (pintype "bidirectional"))
      (node (ref "J6") (pin "13") (pinfunction "11_13") (pintype "bidirectional"))
      (node (ref "J6") (pin "14") (pinfunction "12_14") (pintype "bidirectional"))
      (node (ref "J6") (pin "4") (pinfunction "4_4") (pintype "bidirectional"))
      (node (ref "J6") (pin "6") (pinfunction "6_6") (pintype "bidirectional"))
      (node (ref "JP1") (pin "P$12") (pinfunction "GND4_P$12") (pintype "bidirectional"))
      (node (ref "JP1") (pin "P$18") (pinfunction "B2_P$18") (pintype "bidirectional"))
      (node (ref "JP1") (pin "P$19") (pinfunction "B1_P$19") (pintype "bidirectional"))
      (node (ref "JP1") (pin "P$20") (pinfunction "B0_P$20") (pintype "bidirectional"))
      (node (ref "JP1") (pin "P$27") (pinfunction "G1_P$27") (pintype "bidirectional"))
      (node (ref "JP1") (pin "P$28") (pinfunction "G0_P$28") (pintype "bidirectional"))
      (node (ref "JP1") (pin "P$34") (pinfunction "R2_P$34") (pintype "bidirectional"))
      (node (ref "JP1") (pin "P$35") (pinfunction "R1_P$35") (pintype "bidirectional"))
      (node (ref "JP1") (pin "P$36") (pinfunction "R0_P$36") (pintype "bidirectional"))
      (node (ref "JP1") (pin "P$38") (pinfunction "GND3_P$38") (pintype "bidirectional"))
      (node (ref "JP1") (pin "P$41") (pinfunction "GND5_P$41") (pintype "bidirectional"))
      (node (ref "JP1") (pin "P$42") (pinfunction "GND6_P$42") (pintype "bidirectional"))
      (node (ref "JP1") (pin "P$5") (pinfunction "GND2_P$5") (pintype "bidirectional"))
      (node (ref "K1") (pin "1") (pinfunction "1_1") (pintype "passive"))
      (node (ref "K4") (pin "1") (pinfunction "1_1") (pintype "passive"))
      (node (ref "LED1") (pin "-") (pinfunction "-_-") (pintype "passive"))
      (node (ref "Q5") (pin "2") (pinfunction "E_2") (pintype "passive"))
      (node (ref "R13") (pin "1") (pinfunction "1_1") (pintype "passive"))
      (node (ref "R14") (pin "2") (pinfunction "2_2") (pintype "passive"))
      (node (ref "R15") (pin "1") (pinfunction "1_1") (pintype "passive"))
      (node (ref "R21") (pin "2") (pinfunction "2_2") (pintype "passive"))
      (node (ref "R29") (pin "2") (pinfunction "2_2") (pintype "passive"))
      (node (ref "R31") (pin "1") (pinfunction "1_1") (pintype "passive"))
      (node (ref "R58") (pin "1") (pinfunction "1_1") (pintype "passive"))
      (node (ref "SD1") (pin "6") (pinfunction "VSS_6") (pintype "bidirectional"))
      (node (ref "SD1") (pin "G1") (pinfunction "G1_G1") (pintype "bidirectional"))
      (node (ref "SD1") (pin "G2") (pinfunction "G2_G2") (pintype "bidirectional"))
      (node (ref "SD1") (pin "G3") (pinfunction "G3_G3") (pintype "bidirectional"))
      (node (ref "SD1") (pin "G4") (pinfunction "G4_G4") (pintype "bidirectional"))
      (node (ref "U1") (pin "2") (pinfunction "GND_2") (pintype "bidirectional"))
      (node (ref "U11") (pin "7") (pinfunction "GND_7") (pintype "bidirectional"))
      (node (ref "U2") (pin "1") (pinfunction "GND1_1") (pintype "bidirectional"))
      (node (ref "U2") (pin "40") (pinfunction "GND2_40") (pintype "bidirectional"))
      (node (ref "U2") (pin "41") (pinfunction "GND3_41") (pintype "bidirectional"))
      (node (ref "U2") (pin "42") (pinfunction "GND4_42") (pintype "bidirectional"))
      (node (ref "U2") (pin "43") (pinfunction "GND5_43") (pintype "bidirectional"))
      (node (ref "U2") (pin "44") (pinfunction "GND6_44") (pintype "bidirectional"))
      (node (ref "U2") (pin "45") (pinfunction "GND7_45") (pintype "bidirectional"))
      (node (ref "U2") (pin "46") (pinfunction "GND8_46") (pintype "bidirectional"))
      (node (ref "U2") (pin "47") (pinfunction "GND9_47") (pintype "bidirectional"))
      (node (ref "U2") (pin "48") (pinfunction "GND10_48") (pintype "bidirectional"))
      (node (ref "U2") (pin "49") (pinfunction "GND11_49") (pintype "bidirectional"))
      (node (ref "U4") (pin "2") (pinfunction "2-GND_2") (pintype "bidirectional"))
      (node (ref "U6") (pin "1") (pinfunction "GND_1") (pintype "bidirectional"))
    )
    (net (code "59") (name "Net-(C14-Pad1)") (class "Default")
      (node (ref "C14") (pin "1") (pinfunction "1_1") (pintype "passive"))
      (node (ref "C28") (pin "1") (pinfunction "1_1") (pintype "passive"))
      (node (ref "J5") (pin "P$2") (pinfunction "P$2_P$2") (pintype "bidirectional"))
    )
    (net (code "60") (name "Net-(C16-Pad1)") (class "Default")
      (node (ref "C16") (pin "1") (pinfunction "1_1") (pintype "passive"))
      (node (ref "C27") (pin "1") (pinfunction "1_1") (pintype "passive"))
      (node (ref "J5") (pin "P$1") (pinfunction "P$1_P$1") (pintype "bidirectional"))
    )
    (net (code "61") (name "Net-(D6-+)") (class "Default")
      (node (ref "D6") (pin "1") (pinfunction "+_1") (pintype "passive"))
      (node (ref "L5") (pin "2") (pinfunction "2_2") (pintype "bidirectional"))
      (node (ref "U4") (pin "1") (pinfunction "1-SW_1") (pintype "bidirectional"))
    )
    (net (code "62") (name "Net-(J3-CC1)") (class "Default")
      (node (ref "J3") (pin "A5") (pinfunction "CC1_A5") (pintype "bidirectional"))
      (node (ref "R13") (pin "2") (pinfunction "2_2") (pintype "passive"))
    )
    (net (code "63") (name "Net-(J3-CC2)") (class "Default")
      (node (ref "J3") (pin "B5") (pinfunction "CC2_B5") (pintype "bidirectional"))
      (node (ref "R14") (pin "1") (pinfunction "1_1") (pintype "passive"))
    )
    (net (code "64") (name "Net-(JP1-DISP)") (class "Default")
      (node (ref "JP1") (pin "P$10") (pinfunction "DISP_P$10") (pintype "bidirectional"))
      (node (ref "R25") (pin "2") (pinfunction "2_2") (pintype "passive"))
    )
    (net (code "65") (name "Net-(LED1-Pad+)") (class "Default")
      (node (ref "LED1") (pin "+") (pinfunction "+_+") (pintype "passive"))
      (node (ref "R3") (pin "1") (pinfunction "1_1") (pintype "passive"))
    )
    (net (code "66") (name "Net-(Q5-B)") (class "Default")
      (node (ref "Q5") (pin "1") (pinfunction "B_1") (pintype "passive"))
      (node (ref "R11") (pin "1") (pinfunction "1_1") (pintype "passive"))
      (node (ref "R58") (pin "2") (pinfunction "2_2") (pintype "passive"))
    )
    (net (code "67") (name "Net-(Q30-G)") (class "Default")
      (node (ref "Q30") (pin "1") (pinfunction "G_1") (pintype "bidirectional"))
      (node (ref "Q5") (pin "3") (pinfunction "C_3") (pintype "passive"))
      (node (ref "R172") (pin "2") (pinfunction "2_2") (pintype "passive"))
    )
    (net (code "68") (name "Net-(SD1-DATA1)") (class "Default")
      (node (ref "R17") (pin "2") (pinfunction "2_2") (pintype "passive"))
      (node (ref "SD1") (pin "8") (pinfunction "DATA1_8") (pintype "bidirectional"))
    )
    (net (code "69") (name "Net-(SD1-DATA2)") (class "Default")
      (node (ref "R16") (pin "2") (pinfunction "2_2") (pintype "passive"))
      (node (ref "SD1") (pin "1") (pinfunction "DATA2_1") (pintype "bidirectional"))
    )
    (net (code "70") (name "Net-(U1-FB)") (class "Default")
      (node (ref "R20") (pin "2") (pinfunction "2_2") (pintype "passive"))
      (node (ref "R21") (pin "1") (pinfunction "1_1") (pintype "passive"))
      (node (ref "U1") (pin "5") (pinfunction "FB_5") (pintype "bidirectional"))
    )
    (net (code "71") (name "Net-(U1-SW)") (class "Default")
      (node (ref "L4") (pin "1") (pinfunction "1_1") (pintype "bidirectional"))
      (node (ref "U1") (pin "3") (pinfunction "SW_3") (pintype "bidirectional"))
    )
    (net (code "72") (name "Net-(U6-RXD)") (class "Default")
      (node (ref "R71") (pin "2") (pinfunction "2_2") (pintype "passive"))
      (node (ref "U6") (pin "3") (pinfunction "RXD_3") (pintype "bidirectional"))
    )
    (net (code "73") (name "Net-(U6-TXD)") (class "Default")
      (node (ref "R72") (pin "2") (pinfunction "2_2") (pintype "passive"))
      (node (ref "U6") (pin "2") (pinfunction "TXD_2") (pintype "bidirectional"))
    )
    (net (code "74") (name "Net-(U11-VON)") (class "Default")
      (node (ref "C27") (pin "2") (pinfunction "2_2") (pintype "passive"))
      (node (ref "U11") (pin "5") (pinfunction "VON_5") (pintype "bidirectional"))
    )
    (net (code "75") (name "Net-(U11-VOP)") (class "Default")
      (node (ref "C28") (pin "2") (pinfunction "2_2") (pintype "passive"))
      (node (ref "U11") (pin "8") (pinfunction "VOP_8") (pintype "bidirectional"))
    )
    (net (code "76") (name "unconnected-(J2-Pad2)") (class "Default")
      (node (ref "J2") (pin "2") (pinfunction "2_2") (pintype "bidirectional"))
    )
    (net (code "77") (name "unconnected-(J3-SBU1-PadA8)") (class "Default")
      (node (ref "J3") (pin "A8") (pinfunction "SBU1_A8") (pintype "bidirectional"))
    )
    (net (code "78") (name "unconnected-(J3-SBU2-PadB8)") (class "Default")
      (node (ref "J3") (pin "B8") (pinfunction "SBU2_B8") (pintype "bidirectional"))
    )
    (net (code "79") (name "unconnected-(J4-P$3-Pad3)") (class "Default")
      (node (ref "J4") (pin "3") (pinfunction "P$3_3") (pintype "bidirectional"))
    )
    (net (code "80") (name "unconnected-(J6-Pad8)") (class "Default")
      (node (ref "J6") (pin "8") (pinfunction "8_8") (pintype "bidirectional"))
    )
    (net (code "81") (name "unconnected-(JP1-NC-PadP$6)") (class "Default")
      (node (ref "JP1") (pin "P$6") (pinfunction "NC_P$6") (pintype "bidirectional"))
    )
    (net (code "82") (name "unconnected-(SD1-CDN-Pad9)") (class "Default")
      (node (ref "SD1") (pin "9") (pinfunction "CDN_9") (pintype "bidirectional"))
    )
    (net (code "83") (name "unconnected-(U2-NC1-Pad28)") (class "Default")
      (node (ref "U2") (pin "28") (pinfunction "NC1_28") (pintype "bidirectional"))
    )
    (net (code "84") (name "unconnected-(U2-NC2-Pad29)") (class "Default")
      (node (ref "U2") (pin "29") (pinfunction "NC2_29") (pintype "bidirectional"))
    )
    (net (code "85") (name "unconnected-(U2-NC3-Pad30)") (class "Default")
      (node (ref "U2") (pin "30") (pinfunction "NC3_30") (pintype "bidirectional"))
    )
    (net (code "86") (name "unconnected-(U6-CTS#-Pad9)") (class "Default")
      (node (ref "U6") (pin "9") (pinfunction "CTS#_9") (pintype "bidirectional"))
    )
    (net (code "87") (name "unconnected-(U6-DCD#-Pad12)") (class "Default")
      (node (ref "U6") (pin "12") (pinfunction "DCD#_12") (pintype "bidirectional"))
    )
    (net (code "88") (name "unconnected-(U6-DSR#-Pad10)") (class "Default")
      (node (ref "U6") (pin "10") (pinfunction "DSR#_10") (pintype "bidirectional"))
    )
    (net (code "89") (name "unconnected-(U6-DTR#-Pad13)") (class "Default")
      (node (ref "U6") (pin "13") (pinfunction "DTR#_13") (pintype "bidirectional"))
    )
    (net (code "90") (name "unconnected-(U6-RI#-Pad11)") (class "Default")
      (node (ref "U6") (pin "11") (pinfunction "RI#_11") (pintype "bidirectional"))
    )
    (net (code "91") (name "unconnected-(U6-RS232-Pad15)") (class "Default")
      (node (ref "U6") (pin "15") (pinfunction "RS232_15") (pintype "bidirectional"))
    )
    (net (code "92") (name "unconnected-(U6-RTS#-Pad14)") (class "Default")
      (node (ref "U6") (pin "14") (pinfunction "RTS#_14") (pintype "bidirectional"))
    )
    (net (code "93") (name "unconnected-(U6-XI-Pad7)") (class "Default")
      (node (ref "U6") (pin "7") (pinfunction "XI_7") (pintype "bidirectional"))
    )
    (net (code "94") (name "unconnected-(U6-XO-Pad8)") (class "Default")
      (node (ref "U6") (pin "8") (pinfunction "XO_8") (pintype "bidirectional"))
    )
    (net (code "95") (name "unconnected-(U11-PE-Pad9)") (class "Default")
      (node (ref "U11") (pin "9") (pinfunction "PE_9") (pintype "bidirectional"))
    )
  )
)
